# DemDis.net
KiCad netlist of a schematic drawn in Altium Designer
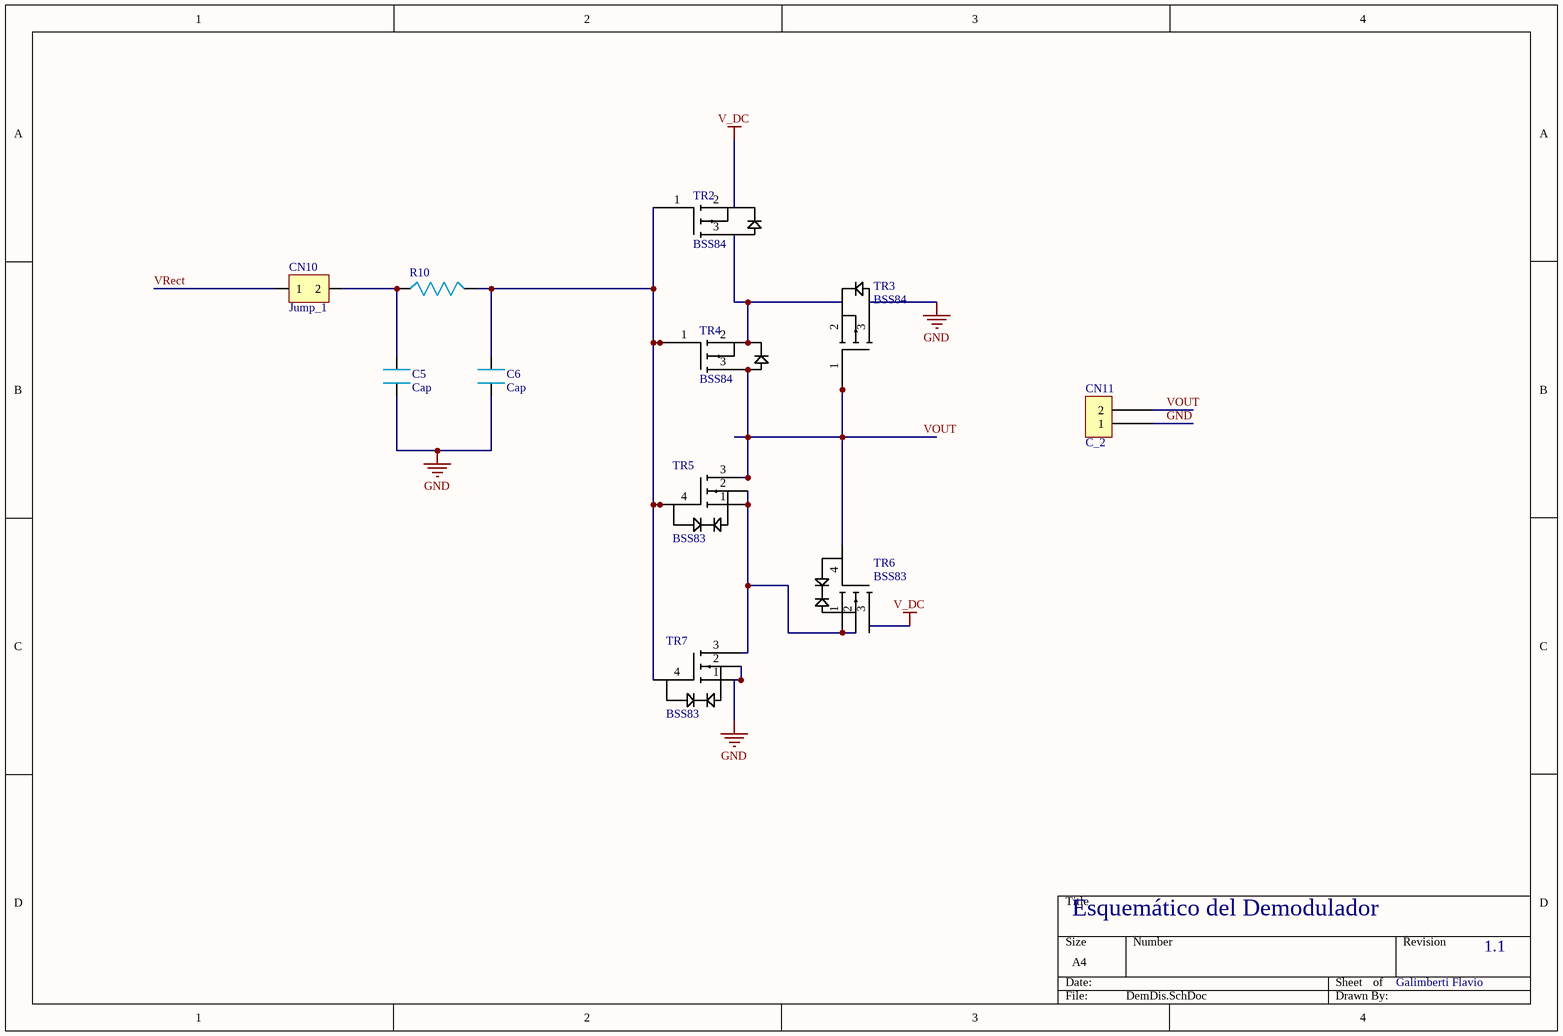
[diagram p0: DemDis.SchDoc]

(export (version "E")
  (design (tool "Eeschema 10.0.6"))
  (components
    (comp (ref "C5")
      (value "Cap")
      (footprint "C_1210")
      (description "Ceramic Capacitor")
      (libsource (lib "BasicosyConectores") (part "Cap"))
    )
    (comp (ref "C6")
      (value "Cap")
      (footprint "C_1210")
      (description "Ceramic Capacitor")
      (libsource (lib "BasicosyConectores") (part "Cap"))
    )
    (comp (ref "CN10")
      (value "Jump_1")
      (footprint "2x1 Pin Array")
      (description "Conector 2 pines")
      (libsource (lib "BasicosyConectores") (part "Jump_1"))
    )
    (comp (ref "CN11")
      (value "C_2")
      (footprint "2x1 Pin Array")
      (description "Conector 2 pines")
      (libsource (lib "BasicosyConectores") (part "C_2"))
    )
    (comp (ref "R10")
      (value "R_1/4")
      (footprint "R_1210")
      (description "Chip Resistor")
      (libsource (lib "BasicosyConectores") (part "R_1/4"))
    )
    (comp (ref "TR2")
      (value "BSS84")
      (footprint "SOT_23")
      (libsource (lib "BasicosyConectores") (part "BSS84"))
    )
    (comp (ref "TR3")
      (value "BSS84")
      (footprint "SOT_23")
      (libsource (lib "BasicosyConectores") (part "BSS84"))
    )
    (comp (ref "TR4")
      (value "BSS84")
      (footprint "SOT_23")
      (libsource (lib "BasicosyConectores") (part "BSS84"))
    )
    (comp (ref "TR5")
      (value "BSS83")
      (footprint "BSS83")
      (libsource (lib "BasicosyConectores") (part "BSS83"))
    )
    (comp (ref "TR6")
      (value "BSS83")
      (footprint "BSS83")
      (libsource (lib "BasicosyConectores") (part "BSS83"))
    )
    (comp (ref "TR7")
      (value "BSS83")
      (footprint "BSS83")
      (libsource (lib "BasicosyConectores") (part "BSS83"))
    )
  )
  (nets
    (net (code "1") (name "/VOUT") (class "Default")
      (node (ref "CN11") (pin "2") (pinfunction "2_2") (pintype "passive"))
      (node (ref "TR3") (pin "1") (pinfunction "g_1") (pintype "passive"))
      (node (ref "TR4") (pin "3") (pinfunction "d_3") (pintype "passive"))
      (node (ref "TR5") (pin "3") (pinfunction "d_3") (pintype "passive"))
      (node (ref "TR6") (pin "4") (pinfunction "g_4") (pintype "passive"))
    )
    (net (code "2") (name "/VRect") (class "Default")
      (node (ref "CN10") (pin "1") (pinfunction "1_1") (pintype "passive"))
    )
    (net (code "3") (name "GND") (class "Default")
      (node (ref "C5") (pin "2") (pinfunction "2_2") (pintype "passive"))
      (node (ref "C6") (pin "2") (pinfunction "2_2") (pintype "passive"))
      (node (ref "CN11") (pin "1") (pinfunction "1_1") (pintype "passive"))
      (node (ref "TR3") (pin "3") (pinfunction "d_3") (pintype "passive"))
      (node (ref "TR7") (pin "1") (pinfunction "s_1") (pintype "passive"))
      (node (ref "TR7") (pin "2") (pinfunction "b_2") (pintype "passive"))
    )
    (net (code "4") (name "Net-(C5-Pad1)") (class "Default")
      (node (ref "C5") (pin "1") (pinfunction "1_1") (pintype "passive"))
      (node (ref "CN10") (pin "2") (pinfunction "2_2") (pintype "passive"))
      (node (ref "R10") (pin "1") (pinfunction "1_1") (pintype "passive"))
    )
    (net (code "5") (name "Net-(TR2-d)") (class "Default")
      (node (ref "TR2") (pin "3") (pinfunction "d_3") (pintype "passive"))
      (node (ref "TR3") (pin "2") (pinfunction "s_2") (pintype "passive"))
      (node (ref "TR4") (pin "2") (pinfunction "s_2") (pintype "passive"))
    )
    (net (code "6") (name "Net-(TR2-g)") (class "Default")
      (node (ref "C6") (pin "1") (pinfunction "1_1") (pintype "passive"))
      (node (ref "R10") (pin "2") (pinfunction "2_2") (pintype "passive"))
      (node (ref "TR2") (pin "1") (pinfunction "g_1") (pintype "passive"))
      (node (ref "TR4") (pin "1") (pinfunction "g_1") (pintype "passive"))
      (node (ref "TR5") (pin "4") (pinfunction "g_4") (pintype "passive"))
      (node (ref "TR7") (pin "4") (pinfunction "g_4") (pintype "passive"))
    )
    (net (code "7") (name "Net-(TR5-b)") (class "Default")
      (node (ref "TR5") (pin "1") (pinfunction "s_1") (pintype "passive"))
      (node (ref "TR5") (pin "2") (pinfunction "b_2") (pintype "passive"))
      (node (ref "TR6") (pin "1") (pinfunction "s_1") (pintype "passive"))
      (node (ref "TR6") (pin "2") (pinfunction "b_2") (pintype "passive"))
      (node (ref "TR7") (pin "3") (pinfunction "d_3") (pintype "passive"))
    )
    (net (code "8") (name "V_DC") (class "Default")
      (node (ref "TR2") (pin "2") (pinfunction "s_2") (pintype "passive"))
      (node (ref "TR6") (pin "3") (pinfunction "d_3") (pintype "passive"))
    )
  )
)
